# west-comms-hardware.net
KiCad netlist of a schematic drawn in EAGLE
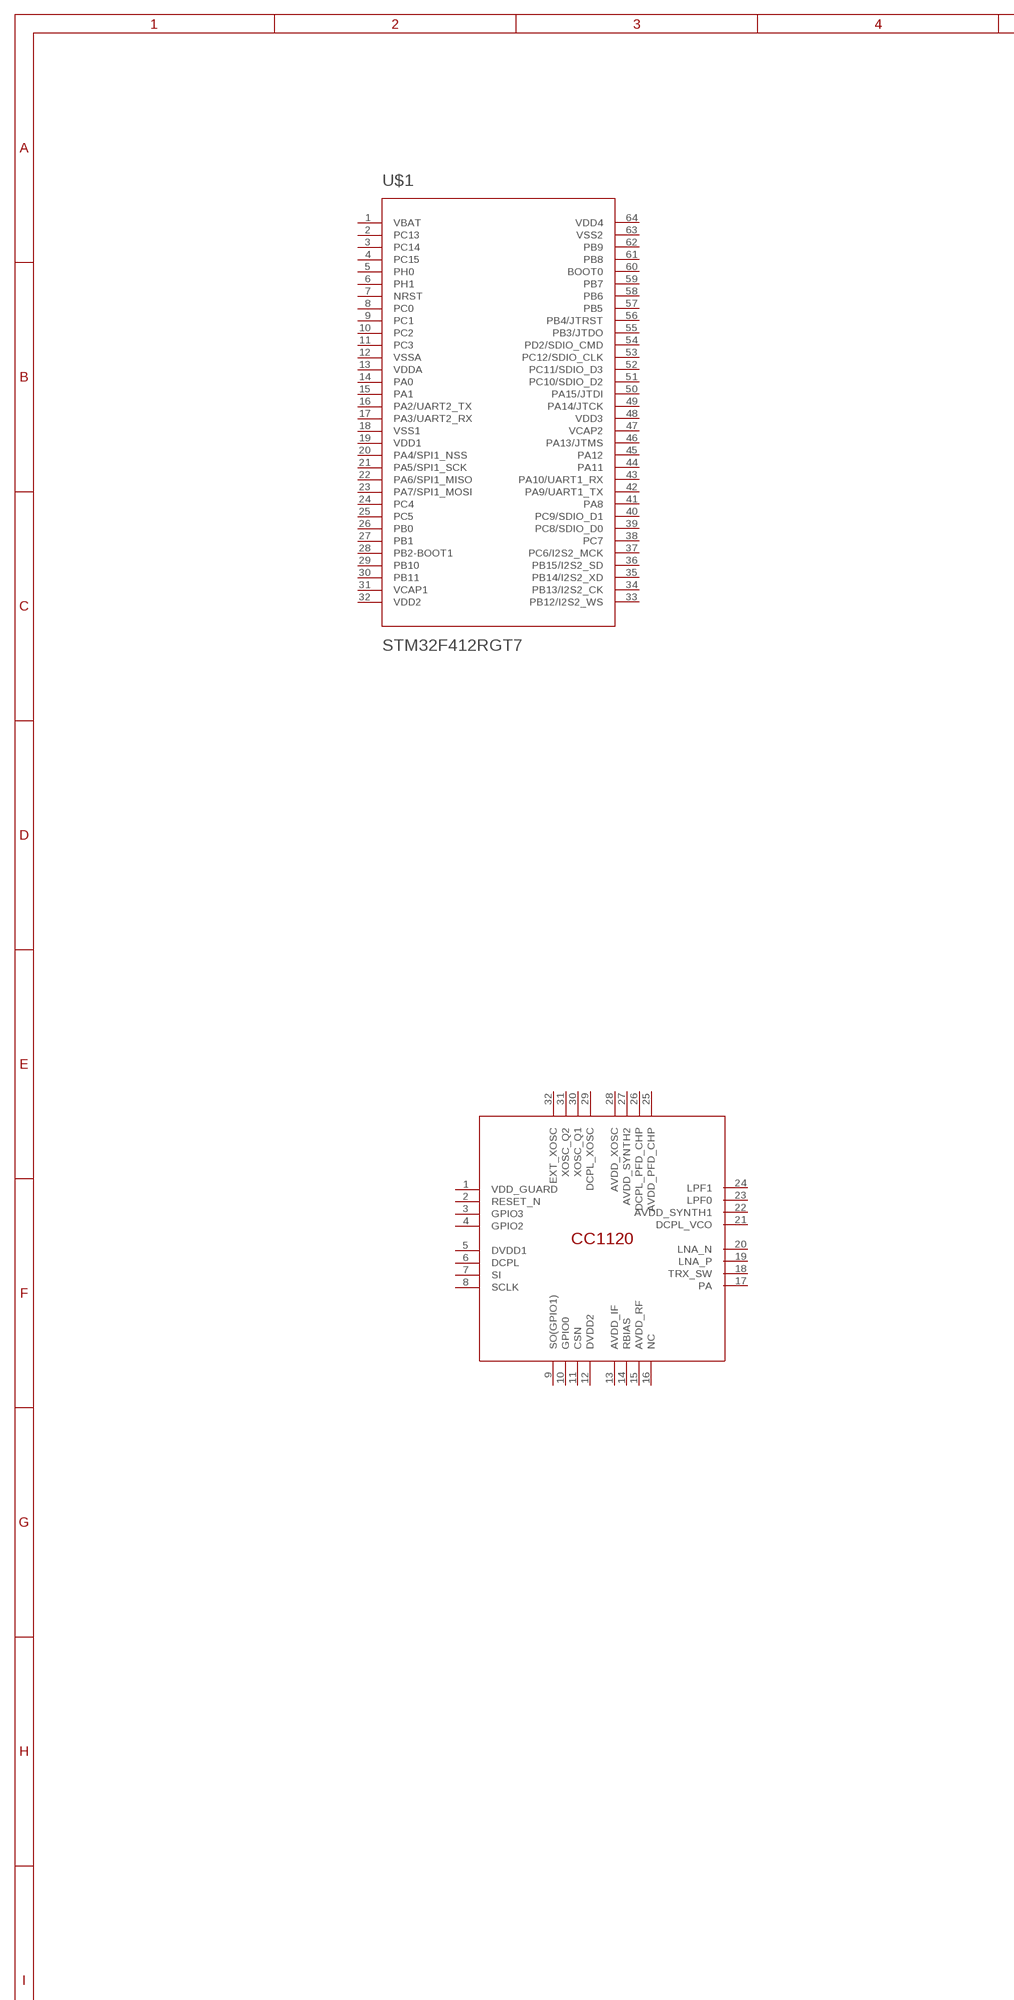
[diagram p0: schematic, sheet 1, part 1 of 2]
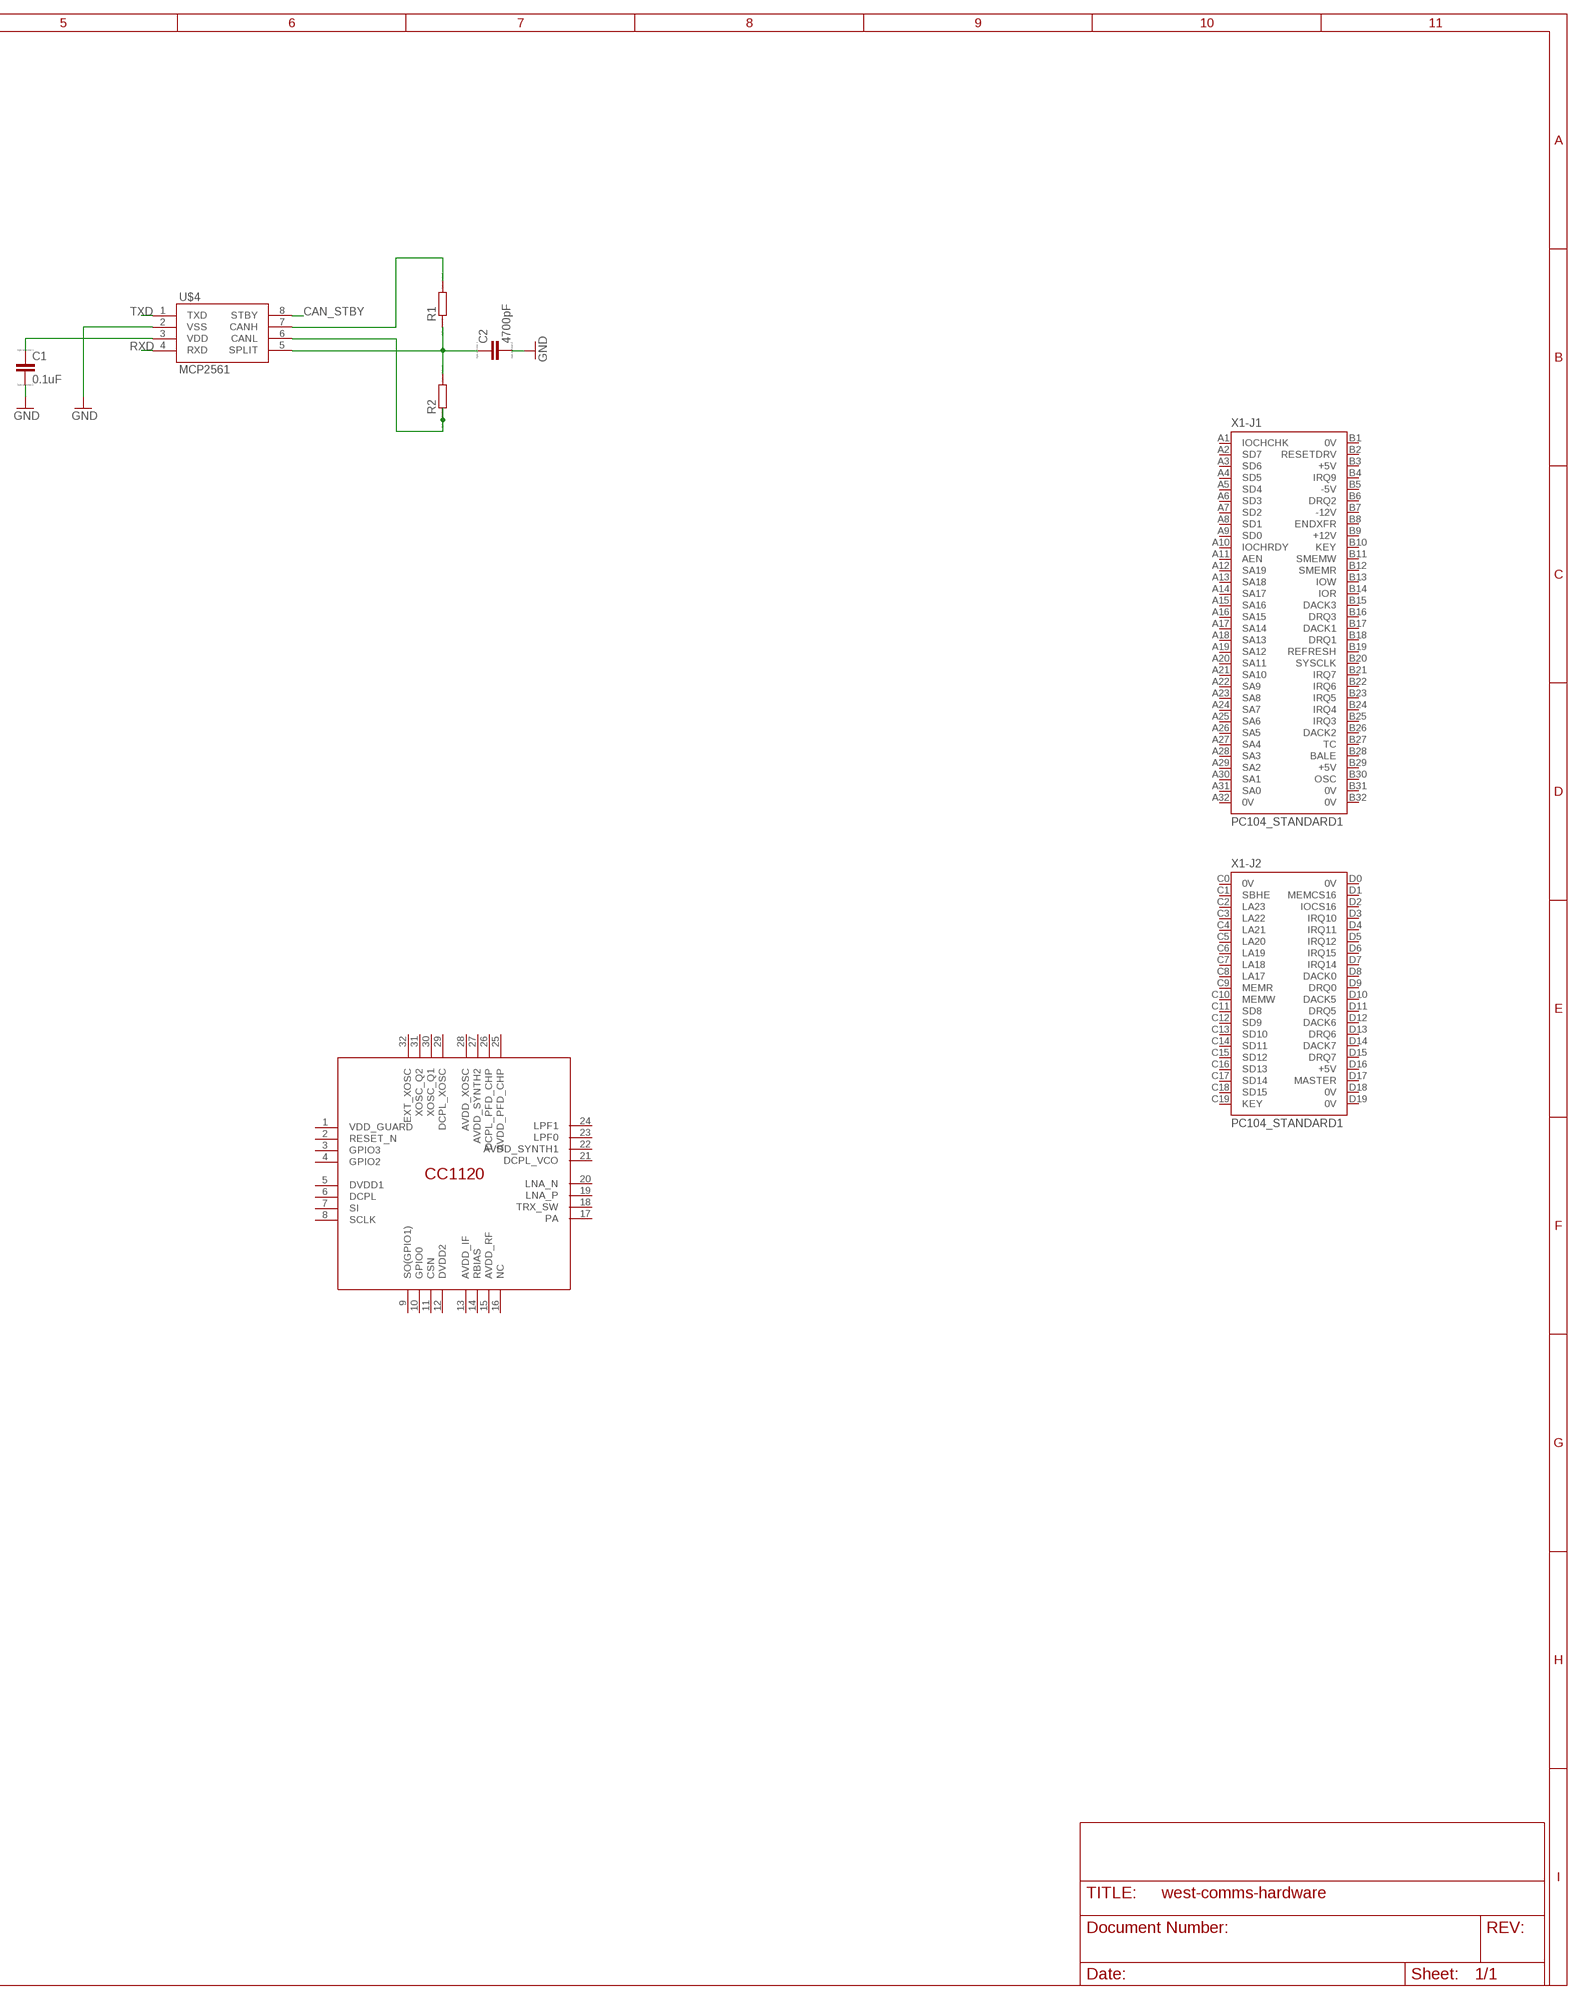
[diagram p1: schematic, sheet 1, part 2 of 2]

(export (version "E")
  (design (tool "Eeschema 10.0.6"))
  (components
    (comp (ref "C1")
      (value "0.1uF")
      (footprint "eagle-import:C0603")
      (libsource (lib "eagle-import") (part "CC0603"))
    )
    (comp (ref "C2")
      (value "4700pF")
      (footprint "eagle-import:C0603")
      (libsource (lib "eagle-import") (part "CC0603"))
    )
    (comp (ref "R1")
      (value "RR0603")
      (footprint "eagle-import:R0603")
      (libsource (lib "eagle-import") (part "RR0603"))
    )
    (comp (ref "R2")
      (value "RR0603")
      (footprint "eagle-import:R0603")
      (libsource (lib "eagle-import") (part "RR0603"))
    )
    (comp (ref "U$1")
      (value "STM32F412RGT7")
      (footprint "eagle-import:TQFP64")
      (libsource (lib "eagle-import") (part "STM32F405RG"))
    )
    (comp (ref "U$2")
      (value "CC1120")
      (footprint "eagle-import:VQFN")
      (libsource (lib "eagle-import") (part "CC1120"))
    )
    (comp (ref "U$3")
      (value "CC1120")
      (footprint "eagle-import:VQFN")
      (libsource (lib "eagle-import") (part "CC1120"))
    )
    (comp (ref "U$4")
      (value "MCP2561")
      (footprint "eagle-import:SO08")
      (libsource (lib "eagle-import") (part "MCP2561"))
    )
    (comp (ref "X1")
      (value "PC104_STANDARD1")
      (footprint "eagle-import:PC104-STANDARD")
      (libsource (lib "eagle-import") (part "PC104_STANDARD1"))
    )
  )
  (nets
    (net (code "1") (name "/CAN_STBY") (class "Default")
      (node (ref "U$4") (pin "8") (pinfunction "STBY_8") (pintype "bidirectional"))
    )
    (net (code "2") (name "/RXD") (class "Default")
      (node (ref "U$4") (pin "4") (pinfunction "RXD_4") (pintype "bidirectional"))
    )
    (net (code "3") (name "/TXD") (class "Default")
      (node (ref "U$4") (pin "1") (pinfunction "TXD_1") (pintype "bidirectional"))
    )
    (net (code "4") (name "GND") (class "Default")
      (node (ref "C1") (pin "2") (pinfunction "2_2") (pintype "passive"))
      (node (ref "C2") (pin "2") (pinfunction "2_2") (pintype "passive"))
      (node (ref "U$4") (pin "2") (pinfunction "VSS_2") (pintype "bidirectional"))
    )
    (net (code "5") (name "Net-(U$4-CANH)") (class "Default")
      (node (ref "R1") (pin "2") (pinfunction "2_2") (pintype "passive"))
      (node (ref "U$4") (pin "7") (pinfunction "CANH_7") (pintype "bidirectional"))
    )
    (net (code "6") (name "Net-(U$4-CANL)") (class "Default")
      (node (ref "R2") (pin "1") (pinfunction "1_1") (pintype "passive"))
      (node (ref "U$4") (pin "6") (pinfunction "CANL_6") (pintype "bidirectional"))
    )
    (net (code "7") (name "Net-(U$4-SPLIT)") (class "Default")
      (node (ref "C2") (pin "1") (pinfunction "1_1") (pintype "passive"))
      (node (ref "R1") (pin "1") (pinfunction "1_1") (pintype "passive"))
      (node (ref "R2") (pin "2") (pinfunction "2_2") (pintype "passive"))
      (node (ref "U$4") (pin "5") (pinfunction "SPLIT_5") (pintype "bidirectional"))
    )
    (net (code "8") (name "Net-(U$4-VDD)") (class "Default")
      (node (ref "C1") (pin "1") (pinfunction "1_1") (pintype "passive"))
      (node (ref "U$4") (pin "3") (pinfunction "VDD_3") (pintype "bidirectional"))
    )
    (net (code "9") (name "unconnected-(U$1-BOOT0-Pad60)") (class "Default")
      (node (ref "U$1") (pin "60") (pinfunction "BOOT0_60") (pintype "bidirectional"))
    )
    (net (code "10") (name "unconnected-(U$1-NRST-Pad7)") (class "Default")
      (node (ref "U$1") (pin "7") (pinfunction "NRST_7") (pintype "bidirectional"))
    )
    (net (code "11") (name "unconnected-(U$1-PA0-Pad14)") (class "Default")
      (node (ref "U$1") (pin "14") (pinfunction "PA0_14") (pintype "bidirectional"))
    )
    (net (code "12") (name "unconnected-(U$1-PA1-Pad15)") (class "Default")
      (node (ref "U$1") (pin "15") (pinfunction "PA1_15") (pintype "bidirectional"))
    )
    (net (code "13") (name "unconnected-(U$1-PA2{slash}UART2_TX-Pad16)") (class "Default")
      (node (ref "U$1") (pin "16") (pinfunction "PA2/UART2_TX_16") (pintype "bidirectional"))
    )
    (net (code "14") (name "unconnected-(U$1-PA3{slash}UART2_RX-Pad17)") (class "Default")
      (node (ref "U$1") (pin "17") (pinfunction "PA3/UART2_RX_17") (pintype "bidirectional"))
    )
    (net (code "15") (name "unconnected-(U$1-PA4{slash}SPI1_NSS-Pad20)") (class "Default")
      (node (ref "U$1") (pin "20") (pinfunction "PA4/SPI1_NSS_20") (pintype "bidirectional"))
    )
    (net (code "16") (name "unconnected-(U$1-PA5{slash}SPI1_SCK-Pad21)") (class "Default")
      (node (ref "U$1") (pin "21") (pinfunction "PA5/SPI1_SCK_21") (pintype "bidirectional"))
    )
    (net (code "17") (name "unconnected-(U$1-PA6{slash}SPI1_MISO-Pad22)") (class "Default")
      (node (ref "U$1") (pin "22") (pinfunction "PA6/SPI1_MISO_22") (pintype "bidirectional"))
    )
    (net (code "18") (name "unconnected-(U$1-PA7{slash}SPI1_MOSI-Pad23)") (class "Default")
      (node (ref "U$1") (pin "23") (pinfunction "PA7/SPI1_MOSI_23") (pintype "bidirectional"))
    )
    (net (code "19") (name "unconnected-(U$1-PA8-Pad41)") (class "Default")
      (node (ref "U$1") (pin "41") (pinfunction "PA8_41") (pintype "bidirectional"))
    )
    (net (code "20") (name "unconnected-(U$1-PA9{slash}UART1_TX-Pad42)") (class "Default")
      (node (ref "U$1") (pin "42") (pinfunction "PA9/UART1_TX_42") (pintype "bidirectional"))
    )
    (net (code "21") (name "unconnected-(U$1-PA10{slash}UART1_RX-Pad43)") (class "Default")
      (node (ref "U$1") (pin "43") (pinfunction "PA10/UART1_RX_43") (pintype "bidirectional"))
    )
    (net (code "22") (name "unconnected-(U$1-PA11-Pad44)") (class "Default")
      (node (ref "U$1") (pin "44") (pinfunction "PA11_44") (pintype "bidirectional"))
    )
    (net (code "23") (name "unconnected-(U$1-PA12-Pad45)") (class "Default")
      (node (ref "U$1") (pin "45") (pinfunction "PA12_45") (pintype "bidirectional"))
    )
    (net (code "24") (name "unconnected-(U$1-PA13{slash}JTMS-Pad46)") (class "Default")
      (node (ref "U$1") (pin "46") (pinfunction "PA13/JTMS_46") (pintype "bidirectional"))
    )
    (net (code "25") (name "unconnected-(U$1-PA14{slash}JTCK-Pad49)") (class "Default")
      (node (ref "U$1") (pin "49") (pinfunction "PA14/JTCK_49") (pintype "bidirectional"))
    )
    (net (code "26") (name "unconnected-(U$1-PA15{slash}JTDI-Pad50)") (class "Default")
      (node (ref "U$1") (pin "50") (pinfunction "PA15/JTDI_50") (pintype "bidirectional"))
    )
    (net (code "27") (name "unconnected-(U$1-PB0-Pad26)") (class "Default")
      (node (ref "U$1") (pin "26") (pinfunction "PB0_26") (pintype "bidirectional"))
    )
    (net (code "28") (name "unconnected-(U$1-PB1-Pad27)") (class "Default")
      (node (ref "U$1") (pin "27") (pinfunction "PB1_27") (pintype "bidirectional"))
    )
    (net (code "29") (name "unconnected-(U$1-PB2-BOOT1-Pad28)") (class "Default")
      (node (ref "U$1") (pin "28") (pinfunction "PB2-BOOT1_28") (pintype "bidirectional"))
    )
    (net (code "30") (name "unconnected-(U$1-PB3{slash}JTDO-Pad55)") (class "Default")
      (node (ref "U$1") (pin "55") (pinfunction "PB3/JTDO_55") (pintype "bidirectional"))
    )
    (net (code "31") (name "unconnected-(U$1-PB4{slash}JTRST-Pad56)") (class "Default")
      (node (ref "U$1") (pin "56") (pinfunction "PB4/JTRST_56") (pintype "bidirectional"))
    )
    (net (code "32") (name "unconnected-(U$1-PB5-Pad57)") (class "Default")
      (node (ref "U$1") (pin "57") (pinfunction "PB5_57") (pintype "bidirectional"))
    )
    (net (code "33") (name "unconnected-(U$1-PB6-Pad58)") (class "Default")
      (node (ref "U$1") (pin "58") (pinfunction "PB6_58") (pintype "bidirectional"))
    )
    (net (code "34") (name "unconnected-(U$1-PB7-Pad59)") (class "Default")
      (node (ref "U$1") (pin "59") (pinfunction "PB7_59") (pintype "bidirectional"))
    )
    (net (code "35") (name "unconnected-(U$1-PB8-Pad61)") (class "Default")
      (node (ref "U$1") (pin "61") (pinfunction "PB8_61") (pintype "bidirectional"))
    )
    (net (code "36") (name "unconnected-(U$1-PB9-Pad62)") (class "Default")
      (node (ref "U$1") (pin "62") (pinfunction "PB9_62") (pintype "bidirectional"))
    )
    (net (code "37") (name "unconnected-(U$1-PB10-Pad29)") (class "Default")
      (node (ref "U$1") (pin "29") (pinfunction "PB10_29") (pintype "bidirectional"))
    )
    (net (code "38") (name "unconnected-(U$1-PB11-Pad30)") (class "Default")
      (node (ref "U$1") (pin "30") (pinfunction "PB11_30") (pintype "bidirectional"))
    )
    (net (code "39") (name "unconnected-(U$1-PB12{slash}I2S2_WS-Pad33)") (class "Default")
      (node (ref "U$1") (pin "33") (pinfunction "PB12/I2S2_WS_33") (pintype "bidirectional"))
    )
    (net (code "40") (name "unconnected-(U$1-PB13{slash}I2S2_CK-Pad34)") (class "Default")
      (node (ref "U$1") (pin "34") (pinfunction "PB13/I2S2_CK_34") (pintype "bidirectional"))
    )
    (net (code "41") (name "unconnected-(U$1-PB14{slash}I2S2_XD-Pad35)") (class "Default")
      (node (ref "U$1") (pin "35") (pinfunction "PB14/I2S2_XD_35") (pintype "bidirectional"))
    )
    (net (code "42") (name "unconnected-(U$1-PB15{slash}I2S2_SD-Pad36)") (class "Default")
      (node (ref "U$1") (pin "36") (pinfunction "PB15/I2S2_SD_36") (pintype "bidirectional"))
    )
    (net (code "43") (name "unconnected-(U$1-PC0-Pad8)") (class "Default")
      (node (ref "U$1") (pin "8") (pinfunction "PC0_8") (pintype "bidirectional"))
    )
    (net (code "44") (name "unconnected-(U$1-PC1-Pad9)") (class "Default")
      (node (ref "U$1") (pin "9") (pinfunction "PC1_9") (pintype "bidirectional"))
    )
    (net (code "45") (name "unconnected-(U$1-PC2-Pad10)") (class "Default")
      (node (ref "U$1") (pin "10") (pinfunction "PC2_10") (pintype "bidirectional"))
    )
    (net (code "46") (name "unconnected-(U$1-PC3-Pad11)") (class "Default")
      (node (ref "U$1") (pin "11") (pinfunction "PC3_11") (pintype "bidirectional"))
    )
    (net (code "47") (name "unconnected-(U$1-PC4-Pad24)") (class "Default")
      (node (ref "U$1") (pin "24") (pinfunction "PC4_24") (pintype "bidirectional"))
    )
    (net (code "48") (name "unconnected-(U$1-PC5-Pad25)") (class "Default")
      (node (ref "U$1") (pin "25") (pinfunction "PC5_25") (pintype "bidirectional"))
    )
    (net (code "49") (name "unconnected-(U$1-PC6{slash}I2S2_MCK-Pad37)") (class "Default")
      (node (ref "U$1") (pin "37") (pinfunction "PC6/I2S2_MCK_37") (pintype "bidirectional"))
    )
    (net (code "50") (name "unconnected-(U$1-PC7-Pad38)") (class "Default")
      (node (ref "U$1") (pin "38") (pinfunction "PC7_38") (pintype "bidirectional"))
    )
    (net (code "51") (name "unconnected-(U$1-PC8{slash}SDIO_D0-Pad39)") (class "Default")
      (node (ref "U$1") (pin "39") (pinfunction "PC8/SDIO_D0_39") (pintype "bidirectional"))
    )
    (net (code "52") (name "unconnected-(U$1-PC9{slash}SDIO_D1-Pad40)") (class "Default")
      (node (ref "U$1") (pin "40") (pinfunction "PC9/SDIO_D1_40") (pintype "bidirectional"))
    )
    (net (code "53") (name "unconnected-(U$1-PC10{slash}SDIO_D2-Pad51)") (class "Default")
      (node (ref "U$1") (pin "51") (pinfunction "PC10/SDIO_D2_51") (pintype "bidirectional"))
    )
    (net (code "54") (name "unconnected-(U$1-PC11{slash}SDIO_D3-Pad52)") (class "Default")
      (node (ref "U$1") (pin "52") (pinfunction "PC11/SDIO_D3_52") (pintype "bidirectional"))
    )
    (net (code "55") (name "unconnected-(U$1-PC12{slash}SDIO_CLK-Pad53)") (class "Default")
      (node (ref "U$1") (pin "53") (pinfunction "PC12/SDIO_CLK_53") (pintype "bidirectional"))
    )
    (net (code "56") (name "unconnected-(U$1-PC13-Pad2)") (class "Default")
      (node (ref "U$1") (pin "2") (pinfunction "PC13_2") (pintype "bidirectional"))
    )
    (net (code "57") (name "unconnected-(U$1-PC14-Pad3)") (class "Default")
      (node (ref "U$1") (pin "3") (pinfunction "PC14_3") (pintype "bidirectional"))
    )
    (net (code "58") (name "unconnected-(U$1-PC15-Pad4)") (class "Default")
      (node (ref "U$1") (pin "4") (pinfunction "PC15_4") (pintype "bidirectional"))
    )
    (net (code "59") (name "unconnected-(U$1-PD2{slash}SDIO_CMD-Pad54)") (class "Default")
      (node (ref "U$1") (pin "54") (pinfunction "PD2/SDIO_CMD_54") (pintype "bidirectional"))
    )
    (net (code "60") (name "unconnected-(U$1-PH0-Pad5)") (class "Default")
      (node (ref "U$1") (pin "5") (pinfunction "PH0_5") (pintype "bidirectional"))
    )
    (net (code "61") (name "unconnected-(U$1-PH1-Pad6)") (class "Default")
      (node (ref "U$1") (pin "6") (pinfunction "PH1_6") (pintype "bidirectional"))
    )
    (net (code "62") (name "unconnected-(U$1-VBAT-Pad1)") (class "Default")
      (node (ref "U$1") (pin "1") (pinfunction "VBAT_1") (pintype "bidirectional"))
    )
    (net (code "63") (name "unconnected-(U$1-VCAP1-Pad31)") (class "Default")
      (node (ref "U$1") (pin "31") (pinfunction "VCAP1_31") (pintype "bidirectional"))
    )
    (net (code "64") (name "unconnected-(U$1-VCAP2-Pad47)") (class "Default")
      (node (ref "U$1") (pin "47") (pinfunction "VCAP2_47") (pintype "bidirectional"))
    )
    (net (code "65") (name "unconnected-(U$1-VDD1-Pad19)") (class "Default")
      (node (ref "U$1") (pin "19") (pinfunction "VDD1_19") (pintype "bidirectional"))
    )
    (net (code "66") (name "unconnected-(U$1-VDD2-Pad32)") (class "Default")
      (node (ref "U$1") (pin "32") (pinfunction "VDD2_32") (pintype "bidirectional"))
    )
    (net (code "67") (name "unconnected-(U$1-VDD3-Pad48)") (class "Default")
      (node (ref "U$1") (pin "48") (pinfunction "VDD3_48") (pintype "bidirectional"))
    )
    (net (code "68") (name "unconnected-(U$1-VDD4-Pad64)") (class "Default")
      (node (ref "U$1") (pin "64") (pinfunction "VDD4_64") (pintype "bidirectional"))
    )
    (net (code "69") (name "unconnected-(U$1-VDDA-Pad13)") (class "Default")
      (node (ref "U$1") (pin "13") (pinfunction "VDDA_13") (pintype "bidirectional"))
    )
    (net (code "70") (name "unconnected-(U$1-VSS1-Pad18)") (class "Default")
      (node (ref "U$1") (pin "18") (pinfunction "VSS1_18") (pintype "bidirectional"))
    )
    (net (code "71") (name "unconnected-(U$1-VSS2-Pad63)") (class "Default")
      (node (ref "U$1") (pin "63") (pinfunction "VSS2_63") (pintype "bidirectional"))
    )
    (net (code "72") (name "unconnected-(U$1-VSSA-Pad12)") (class "Default")
      (node (ref "U$1") (pin "12") (pinfunction "VSSA_12") (pintype "bidirectional"))
    )
    (net (code "73") (name "unconnected-(U$2-AVDD_IF-Pad13)") (class "Default")
      (node (ref "U$2") (pin "13") (pinfunction "AVDD_IF_13") (pintype "bidirectional"))
    )
    (net (code "74") (name "unconnected-(U$2-AVDD_PFD_CHP-Pad25)") (class "Default")
      (node (ref "U$2") (pin "25") (pinfunction "AVDD_PFD_CHP_25") (pintype "bidirectional"))
    )
    (net (code "75") (name "unconnected-(U$2-AVDD_RF-Pad15)") (class "Default")
      (node (ref "U$2") (pin "15") (pinfunction "AVDD_RF_15") (pintype "bidirectional"))
    )
    (net (code "76") (name "unconnected-(U$2-AVDD_SYNTH1-Pad22)") (class "Default")
      (node (ref "U$2") (pin "22") (pinfunction "AVDD_SYNTH1_22") (pintype "bidirectional"))
    )
    (net (code "77") (name "unconnected-(U$2-AVDD_SYNTH2-Pad27)") (class "Default")
      (node (ref "U$2") (pin "27") (pinfunction "AVDD_SYNTH2_27") (pintype "bidirectional"))
    )
    (net (code "78") (name "unconnected-(U$2-AVDD_XOSC-Pad28)") (class "Default")
      (node (ref "U$2") (pin "28") (pinfunction "AVDD_XOSC_28") (pintype "bidirectional"))
    )
    (net (code "79") (name "unconnected-(U$2-CSN-Pad11)") (class "Default")
      (node (ref "U$2") (pin "11") (pinfunction "CSN_11") (pintype "bidirectional"))
    )
    (net (code "80") (name "unconnected-(U$2-DCPL-Pad6)") (class "Default")
      (node (ref "U$2") (pin "6") (pinfunction "DCPL_6") (pintype "bidirectional"))
    )
    (net (code "81") (name "unconnected-(U$2-DCPL_PFD_CHP-Pad26)") (class "Default")
      (node (ref "U$2") (pin "26") (pinfunction "DCPL_PFD_CHP_26") (pintype "bidirectional"))
    )
    (net (code "82") (name "unconnected-(U$2-DCPL_VCO-Pad21)") (class "Default")
      (node (ref "U$2") (pin "21") (pinfunction "DCPL_VCO_21") (pintype "bidirectional"))
    )
    (net (code "83") (name "unconnected-(U$2-DCPL_XOSC-Pad29)") (class "Default")
      (node (ref "U$2") (pin "29") (pinfunction "DCPL_XOSC_29") (pintype "bidirectional"))
    )
    (net (code "84") (name "unconnected-(U$2-DVDD1-Pad5)") (class "Default")
      (node (ref "U$2") (pin "5") (pinfunction "DVDD1_5") (pintype "bidirectional"))
    )
    (net (code "85") (name "unconnected-(U$2-DVDD2-Pad12)") (class "Default")
      (node (ref "U$2") (pin "12") (pinfunction "DVDD2_12") (pintype "bidirectional"))
    )
    (net (code "86") (name "unconnected-(U$2-EXT_XOSC-Pad32)") (class "Default")
      (node (ref "U$2") (pin "32") (pinfunction "EXT_XOSC_32") (pintype "bidirectional"))
    )
    (net (code "87") (name "unconnected-(U$2-GPIO0-Pad10)") (class "Default")
      (node (ref "U$2") (pin "10") (pinfunction "GPIO0_10") (pintype "bidirectional"))
    )
    (net (code "88") (name "unconnected-(U$2-GPIO2-Pad4)") (class "Default")
      (node (ref "U$2") (pin "4") (pinfunction "GPIO2_4") (pintype "bidirectional"))
    )
    (net (code "89") (name "unconnected-(U$2-GPIO3-Pad3)") (class "Default")
      (node (ref "U$2") (pin "3") (pinfunction "GPIO3_3") (pintype "bidirectional"))
    )
    (net (code "90") (name "unconnected-(U$2-LNA_N-Pad20)") (class "Default")
      (node (ref "U$2") (pin "20") (pinfunction "LNA_N_20") (pintype "bidirectional"))
    )
    (net (code "91") (name "unconnected-(U$2-LNA_P-Pad19)") (class "Default")
      (node (ref "U$2") (pin "19") (pinfunction "LNA_P_19") (pintype "bidirectional"))
    )
    (net (code "92") (name "unconnected-(U$2-LPF0-Pad23)") (class "Default")
      (node (ref "U$2") (pin "23") (pinfunction "LPF0_23") (pintype "bidirectional"))
    )
    (net (code "93") (name "unconnected-(U$2-LPF1-Pad24)") (class "Default")
      (node (ref "U$2") (pin "24") (pinfunction "LPF1_24") (pintype "bidirectional"))
    )
    (net (code "94") (name "unconnected-(U$2-NC-Pad16)") (class "Default")
      (node (ref "U$2") (pin "16") (pinfunction "NC_16") (pintype "bidirectional"))
    )
    (net (code "95") (name "unconnected-(U$2-PA-Pad17)") (class "Default")
      (node (ref "U$2") (pin "17") (pinfunction "PA_17") (pintype "bidirectional"))
    )
    (net (code "96") (name "unconnected-(U$2-RBIAS-Pad14)") (class "Default")
      (node (ref "U$2") (pin "14") (pinfunction "RBIAS_14") (pintype "bidirectional"))
    )
    (net (code "97") (name "unconnected-(U$2-RESET_N-Pad2)") (class "Default")
      (node (ref "U$2") (pin "2") (pinfunction "RESET_N_2") (pintype "bidirectional"))
    )
    (net (code "98") (name "unconnected-(U$2-SCLK-Pad8)") (class "Default")
      (node (ref "U$2") (pin "8") (pinfunction "SCLK_8") (pintype "bidirectional"))
    )
    (net (code "99") (name "unconnected-(U$2-SI-Pad7)") (class "Default")
      (node (ref "U$2") (pin "7") (pinfunction "SI_7") (pintype "bidirectional"))
    )
    (net (code "100") (name "unconnected-(U$2-SO(GPIO1)-Pad9)") (class "Default")
      (node (ref "U$2") (pin "9") (pinfunction "SO(GPIO1)_9") (pintype "bidirectional"))
    )
    (net (code "101") (name "unconnected-(U$2-TRX_SW-Pad18)") (class "Default")
      (node (ref "U$2") (pin "18") (pinfunction "TRX_SW_18") (pintype "bidirectional"))
    )
    (net (code "102") (name "unconnected-(U$2-VDD_GUARD-Pad1)") (class "Default")
      (node (ref "U$2") (pin "1") (pinfunction "VDD_GUARD_1") (pintype "bidirectional"))
    )
    (net (code "103") (name "unconnected-(U$2-XOSC_Q1-Pad30)") (class "Default")
      (node (ref "U$2") (pin "30") (pinfunction "XOSC_Q1_30") (pintype "bidirectional"))
    )
    (net (code "104") (name "unconnected-(U$2-XOSC_Q2-Pad31)") (class "Default")
      (node (ref "U$2") (pin "31") (pinfunction "XOSC_Q2_31") (pintype "bidirectional"))
    )
    (net (code "105") (name "unconnected-(U$3-AVDD_IF-Pad13)") (class "Default")
      (node (ref "U$3") (pin "13") (pinfunction "AVDD_IF_13") (pintype "bidirectional"))
    )
    (net (code "106") (name "unconnected-(U$3-AVDD_PFD_CHP-Pad25)") (class "Default")
      (node (ref "U$3") (pin "25") (pinfunction "AVDD_PFD_CHP_25") (pintype "bidirectional"))
    )
    (net (code "107") (name "unconnected-(U$3-AVDD_RF-Pad15)") (class "Default")
      (node (ref "U$3") (pin "15") (pinfunction "AVDD_RF_15") (pintype "bidirectional"))
    )
    (net (code "108") (name "unconnected-(U$3-AVDD_SYNTH1-Pad22)") (class "Default")
      (node (ref "U$3") (pin "22") (pinfunction "AVDD_SYNTH1_22") (pintype "bidirectional"))
    )
    (net (code "109") (name "unconnected-(U$3-AVDD_SYNTH2-Pad27)") (class "Default")
      (node (ref "U$3") (pin "27") (pinfunction "AVDD_SYNTH2_27") (pintype "bidirectional"))
    )
    (net (code "110") (name "unconnected-(U$3-AVDD_XOSC-Pad28)") (class "Default")
      (node (ref "U$3") (pin "28") (pinfunction "AVDD_XOSC_28") (pintype "bidirectional"))
    )
    (net (code "111") (name "unconnected-(U$3-CSN-Pad11)") (class "Default")
      (node (ref "U$3") (pin "11") (pinfunction "CSN_11") (pintype "bidirectional"))
    )
    (net (code "112") (name "unconnected-(U$3-DCPL-Pad6)") (class "Default")
      (node (ref "U$3") (pin "6") (pinfunction "DCPL_6") (pintype "bidirectional"))
    )
    (net (code "113") (name "unconnected-(U$3-DCPL_PFD_CHP-Pad26)") (class "Default")
      (node (ref "U$3") (pin "26") (pinfunction "DCPL_PFD_CHP_26") (pintype "bidirectional"))
    )
    (net (code "114") (name "unconnected-(U$3-DCPL_VCO-Pad21)") (class "Default")
      (node (ref "U$3") (pin "21") (pinfunction "DCPL_VCO_21") (pintype "bidirectional"))
    )
    (net (code "115") (name "unconnected-(U$3-DCPL_XOSC-Pad29)") (class "Default")
      (node (ref "U$3") (pin "29") (pinfunction "DCPL_XOSC_29") (pintype "bidirectional"))
    )
    (net (code "116") (name "unconnected-(U$3-DVDD1-Pad5)") (class "Default")
      (node (ref "U$3") (pin "5") (pinfunction "DVDD1_5") (pintype "bidirectional"))
    )
    (net (code "117") (name "unconnected-(U$3-DVDD2-Pad12)") (class "Default")
      (node (ref "U$3") (pin "12") (pinfunction "DVDD2_12") (pintype "bidirectional"))
    )
    (net (code "118") (name "unconnected-(U$3-EXT_XOSC-Pad32)") (class "Default")
      (node (ref "U$3") (pin "32") (pinfunction "EXT_XOSC_32") (pintype "bidirectional"))
    )
    (net (code "119") (name "unconnected-(U$3-GPIO0-Pad10)") (class "Default")
      (node (ref "U$3") (pin "10") (pinfunction "GPIO0_10") (pintype "bidirectional"))
    )
    (net (code "120") (name "unconnected-(U$3-GPIO2-Pad4)") (class "Default")
      (node (ref "U$3") (pin "4") (pinfunction "GPIO2_4") (pintype "bidirectional"))
    )
    (net (code "121") (name "unconnected-(U$3-GPIO3-Pad3)") (class "Default")
      (node (ref "U$3") (pin "3") (pinfunction "GPIO3_3") (pintype "bidirectional"))
    )
    (net (code "122") (name "unconnected-(U$3-LNA_N-Pad20)") (class "Default")
      (node (ref "U$3") (pin "20") (pinfunction "LNA_N_20") (pintype "bidirectional"))
    )
    (net (code "123") (name "unconnected-(U$3-LNA_P-Pad19)") (class "Default")
      (node (ref "U$3") (pin "19") (pinfunction "LNA_P_19") (pintype "bidirectional"))
    )
    (net (code "124") (name "unconnected-(U$3-LPF0-Pad23)") (class "Default")
      (node (ref "U$3") (pin "23") (pinfunction "LPF0_23") (pintype "bidirectional"))
    )
    (net (code "125") (name "unconnected-(U$3-LPF1-Pad24)") (class "Default")
      (node (ref "U$3") (pin "24") (pinfunction "LPF1_24") (pintype "bidirectional"))
    )
    (net (code "126") (name "unconnected-(U$3-NC-Pad16)") (class "Default")
      (node (ref "U$3") (pin "16") (pinfunction "NC_16") (pintype "bidirectional"))
    )
    (net (code "127") (name "unconnected-(U$3-PA-Pad17)") (class "Default")
      (node (ref "U$3") (pin "17") (pinfunction "PA_17") (pintype "bidirectional"))
    )
    (net (code "128") (name "unconnected-(U$3-RBIAS-Pad14)") (class "Default")
      (node (ref "U$3") (pin "14") (pinfunction "RBIAS_14") (pintype "bidirectional"))
    )
    (net (code "129") (name "unconnected-(U$3-RESET_N-Pad2)") (class "Default")
      (node (ref "U$3") (pin "2") (pinfunction "RESET_N_2") (pintype "bidirectional"))
    )
    (net (code "130") (name "unconnected-(U$3-SCLK-Pad8)") (class "Default")
      (node (ref "U$3") (pin "8") (pinfunction "SCLK_8") (pintype "bidirectional"))
    )
    (net (code "131") (name "unconnected-(U$3-SI-Pad7)") (class "Default")
      (node (ref "U$3") (pin "7") (pinfunction "SI_7") (pintype "bidirectional"))
    )
    (net (code "132") (name "unconnected-(U$3-SO(GPIO1)-Pad9)") (class "Default")
      (node (ref "U$3") (pin "9") (pinfunction "SO(GPIO1)_9") (pintype "bidirectional"))
    )
    (net (code "133") (name "unconnected-(U$3-TRX_SW-Pad18)") (class "Default")
      (node (ref "U$3") (pin "18") (pinfunction "TRX_SW_18") (pintype "bidirectional"))
    )
    (net (code "134") (name "unconnected-(U$3-VDD_GUARD-Pad1)") (class "Default")
      (node (ref "U$3") (pin "1") (pinfunction "VDD_GUARD_1") (pintype "bidirectional"))
    )
    (net (code "135") (name "unconnected-(U$3-XOSC_Q1-Pad30)") (class "Default")
      (node (ref "U$3") (pin "30") (pinfunction "XOSC_Q1_30") (pintype "bidirectional"))
    )
    (net (code "136") (name "unconnected-(U$3-XOSC_Q2-Pad31)") (class "Default")
      (node (ref "U$3") (pin "31") (pinfunction "XOSC_Q2_31") (pintype "bidirectional"))
    )
    (net (code "137") (name "unconnected-(X1A-+5V-PadB3)") (class "Default")
      (node (ref "X1") (pin "B3") (pinfunction "+5V_B3") (pintype "passive"))
    )
    (net (code "138") (name "unconnected-(X1A-+5V-PadB29)") (class "Default")
      (node (ref "X1") (pin "B29") (pinfunction "+5V_B29") (pintype "passive"))
    )
    (net (code "139") (name "unconnected-(X1A-+12V-PadB9)") (class "Default")
      (node (ref "X1") (pin "B9") (pinfunction "+12V_B9") (pintype "passive"))
    )
    (net (code "140") (name "unconnected-(X1A--5V-PadB5)") (class "Default")
      (node (ref "X1") (pin "B5") (pinfunction "-5V_B5") (pintype "passive"))
    )
    (net (code "141") (name "unconnected-(X1A--12V-PadB7)") (class "Default")
      (node (ref "X1") (pin "B7") (pinfunction "-12V_B7") (pintype "passive"))
    )
    (net (code "142") (name "unconnected-(X1A-0V-PadA32)") (class "Default")
      (node (ref "X1") (pin "A32") (pinfunction "0V_A32") (pintype "passive"))
    )
    (net (code "143") (name "unconnected-(X1A-0V-PadB1)") (class "Default")
      (node (ref "X1") (pin "B1") (pinfunction "0V_B1") (pintype "passive"))
    )
    (net (code "144") (name "unconnected-(X1A-0V-PadB31)") (class "Default")
      (node (ref "X1") (pin "B31") (pinfunction "0V_B31") (pintype "passive"))
    )
    (net (code "145") (name "unconnected-(X1A-0V-PadB32)") (class "Default")
      (node (ref "X1") (pin "B32") (pinfunction "0V_B32") (pintype "passive"))
    )
    (net (code "146") (name "unconnected-(X1A-AEN-PadA11)") (class "Default")
      (node (ref "X1") (pin "A11") (pinfunction "AEN_A11") (pintype "passive"))
    )
    (net (code "147") (name "unconnected-(X1A-BALE-PadB28)") (class "Default")
      (node (ref "X1") (pin "B28") (pinfunction "BALE_B28") (pintype "passive"))
    )
    (net (code "148") (name "unconnected-(X1A-DACK1-PadB17)") (class "Default")
      (node (ref "X1") (pin "B17") (pinfunction "DACK1_B17") (pintype "passive"))
    )
    (net (code "149") (name "unconnected-(X1A-DACK2-PadB26)") (class "Default")
      (node (ref "X1") (pin "B26") (pinfunction "DACK2_B26") (pintype "passive"))
    )
    (net (code "150") (name "unconnected-(X1A-DACK3-PadB15)") (class "Default")
      (node (ref "X1") (pin "B15") (pinfunction "DACK3_B15") (pintype "passive"))
    )
    (net (code "151") (name "unconnected-(X1A-DRQ1-PadB18)") (class "Default")
      (node (ref "X1") (pin "B18") (pinfunction "DRQ1_B18") (pintype "passive"))
    )
    (net (code "152") (name "unconnected-(X1A-DRQ2-PadB6)") (class "Default")
      (node (ref "X1") (pin "B6") (pinfunction "DRQ2_B6") (pintype "passive"))
    )
    (net (code "153") (name "unconnected-(X1A-DRQ3-PadB16)") (class "Default")
      (node (ref "X1") (pin "B16") (pinfunction "DRQ3_B16") (pintype "passive"))
    )
    (net (code "154") (name "unconnected-(X1A-ENDXFR-PadB8)") (class "Default")
      (node (ref "X1") (pin "B8") (pinfunction "ENDXFR_B8") (pintype "passive"))
    )
    (net (code "155") (name "unconnected-(X1A-IOCHCHK-PadA1)") (class "Default")
      (node (ref "X1") (pin "A1") (pinfunction "IOCHCHK_A1") (pintype "passive"))
    )
    (net (code "156") (name "unconnected-(X1A-IOCHRDY-PadA10)") (class "Default")
      (node (ref "X1") (pin "A10") (pinfunction "IOCHRDY_A10") (pintype "passive"))
    )
    (net (code "157") (name "unconnected-(X1A-IOR-PadB14)") (class "Default")
      (node (ref "X1") (pin "B14") (pinfunction "IOR_B14") (pintype "passive"))
    )
    (net (code "158") (name "unconnected-(X1A-IOW-PadB13)") (class "Default")
      (node (ref "X1") (pin "B13") (pinfunction "IOW_B13") (pintype "passive"))
    )
    (net (code "159") (name "unconnected-(X1A-IRQ3-PadB25)") (class "Default")
      (node (ref "X1") (pin "B25") (pinfunction "IRQ3_B25") (pintype "passive"))
    )
    (net (code "160") (name "unconnected-(X1A-IRQ4-PadB24)") (class "Default")
      (node (ref "X1") (pin "B24") (pinfunction "IRQ4_B24") (pintype "passive"))
    )
    (net (code "161") (name "unconnected-(X1A-IRQ5-PadB23)") (class "Default")
      (node (ref "X1") (pin "B23") (pinfunction "IRQ5_B23") (pintype "passive"))
    )
    (net (code "162") (name "unconnected-(X1A-IRQ6-PadB22)") (class "Default")
      (node (ref "X1") (pin "B22") (pinfunction "IRQ6_B22") (pintype "passive"))
    )
    (net (code "163") (name "unconnected-(X1A-IRQ7-PadB21)") (class "Default")
      (node (ref "X1") (pin "B21") (pinfunction "IRQ7_B21") (pintype "passive"))
    )
    (net (code "164") (name "unconnected-(X1A-IRQ9-PadB4)") (class "Default")
      (node (ref "X1") (pin "B4") (pinfunction "IRQ9_B4") (pintype "passive"))
    )
    (net (code "165") (name "unconnected-(X1A-KEY-PadB10)") (class "Default")
      (node (ref "X1") (pin "B10") (pinfunction "KEY_B10") (pintype "passive"))
    )
    (net (code "166") (name "unconnected-(X1A-OSC-PadB30)") (class "Default")
      (node (ref "X1") (pin "B30") (pinfunction "OSC_B30") (pintype "passive"))
    )
    (net (code "167") (name "unconnected-(X1A-REFRESH-PadB19)") (class "Default")
      (node (ref "X1") (pin "B19") (pinfunction "REFRESH_B19") (pintype "passive"))
    )
    (net (code "168") (name "unconnected-(X1A-RESETDRV-PadB2)") (class "Default")
      (node (ref "X1") (pin "B2") (pinfunction "RESETDRV_B2") (pintype "passive"))
    )
    (net (code "169") (name "unconnected-(X1A-SA0-PadA31)") (class "Default")
      (node (ref "X1") (pin "A31") (pinfunction "SA0_A31") (pintype "passive"))
    )
    (net (code "170") (name "unconnected-(X1A-SA1-PadA30)") (class "Default")
      (node (ref "X1") (pin "A30") (pinfunction "SA1_A30") (pintype "passive"))
    )
    (net (code "171") (name "unconnected-(X1A-SA2-PadA29)") (class "Default")
      (node (ref "X1") (pin "A29") (pinfunction "SA2_A29") (pintype "passive"))
    )
    (net (code "172") (name "unconnected-(X1A-SA3-PadA28)") (class "Default")
      (node (ref "X1") (pin "A28") (pinfunction "SA3_A28") (pintype "passive"))
    )
    (net (code "173") (name "unconnected-(X1A-SA4-PadA27)") (class "Default")
      (node (ref "X1") (pin "A27") (pinfunction "SA4_A27") (pintype "passive"))
    )
    (net (code "174") (name "unconnected-(X1A-SA5-PadA26)") (class "Default")
      (node (ref "X1") (pin "A26") (pinfunction "SA5_A26") (pintype "passive"))
    )
    (net (code "175") (name "unconnected-(X1A-SA6-PadA25)") (class "Default")
      (node (ref "X1") (pin "A25") (pinfunction "SA6_A25") (pintype "passive"))
    )
    (net (code "176") (name "unconnected-(X1A-SA7-PadA24)") (class "Default")
      (node (ref "X1") (pin "A24") (pinfunction "SA7_A24") (pintype "passive"))
    )
    (net (code "177") (name "unconnected-(X1A-SA8-PadA23)") (class "Default")
      (node (ref "X1") (pin "A23") (pinfunction "SA8_A23") (pintype "passive"))
    )
    (net (code "178") (name "unconnected-(X1A-SA9-PadA22)") (class "Default")
      (node (ref "X1") (pin "A22") (pinfunction "SA9_A22") (pintype "passive"))
    )
    (net (code "179") (name "unconnected-(X1A-SA10-PadA21)") (class "Default")
      (node (ref "X1") (pin "A21") (pinfunction "SA10_A21") (pintype "passive"))
    )
    (net (code "180") (name "unconnected-(X1A-SA11-PadA20)") (class "Default")
      (node (ref "X1") (pin "A20") (pinfunction "SA11_A20") (pintype "passive"))
    )
    (net (code "181") (name "unconnected-(X1A-SA12-PadA19)") (class "Default")
      (node (ref "X1") (pin "A19") (pinfunction "SA12_A19") (pintype "passive"))
    )
    (net (code "182") (name "unconnected-(X1A-SA13-PadA18)") (class "Default")
      (node (ref "X1") (pin "A18") (pinfunction "SA13_A18") (pintype "passive"))
    )
    (net (code "183") (name "unconnected-(X1A-SA14-PadA17)") (class "Default")
      (node (ref "X1") (pin "A17") (pinfunction "SA14_A17") (pintype "passive"))
    )
    (net (code "184") (name "unconnected-(X1A-SA15-PadA16)") (class "Default")
      (node (ref "X1") (pin "A16") (pinfunction "SA15_A16") (pintype "passive"))
    )
    (net (code "185") (name "unconnected-(X1A-SA16-PadA15)") (class "Default")
      (node (ref "X1") (pin "A15") (pinfunction "SA16_A15") (pintype "passive"))
    )
    (net (code "186") (name "unconnected-(X1A-SA17-PadA14)") (class "Default")
      (node (ref "X1") (pin "A14") (pinfunction "SA17_A14") (pintype "passive"))
    )
    (net (code "187") (name "unconnected-(X1A-SA18-PadA13)") (class "Default")
      (node (ref "X1") (pin "A13") (pinfunction "SA18_A13") (pintype "passive"))
    )
    (net (code "188") (name "unconnected-(X1A-SA19-PadA12)") (class "Default")
      (node (ref "X1") (pin "A12") (pinfunction "SA19_A12") (pintype "passive"))
    )
    (net (code "189") (name "unconnected-(X1A-SD0-PadA9)") (class "Default")
      (node (ref "X1") (pin "A9") (pinfunction "SD0_A9") (pintype "passive"))
    )
    (net (code "190") (name "unconnected-(X1A-SD1-PadA8)") (class "Default")
      (node (ref "X1") (pin "A8") (pinfunction "SD1_A8") (pintype "passive"))
    )
    (net (code "191") (name "unconnected-(X1A-SD2-PadA7)") (class "Default")
      (node (ref "X1") (pin "A7") (pinfunction "SD2_A7") (pintype "passive"))
    )
    (net (code "192") (name "unconnected-(X1A-SD3-PadA6)") (class "Default")
      (node (ref "X1") (pin "A6") (pinfunction "SD3_A6") (pintype "passive"))
    )
    (net (code "193") (name "unconnected-(X1A-SD4-PadA5)") (class "Default")
      (node (ref "X1") (pin "A5") (pinfunction "SD4_A5") (pintype "passive"))
    )
    (net (code "194") (name "unconnected-(X1A-SD5-PadA4)") (class "Default")
      (node (ref "X1") (pin "A4") (pinfunction "SD5_A4") (pintype "passive"))
    )
    (net (code "195") (name "unconnected-(X1A-SD6-PadA3)") (class "Default")
      (node (ref "X1") (pin "A3") (pinfunction "SD6_A3") (pintype "passive"))
    )
    (net (code "196") (name "unconnected-(X1A-SD7-PadA2)") (class "Default")
      (node (ref "X1") (pin "A2") (pinfunction "SD7_A2") (pintype "passive"))
    )
    (net (code "197") (name "unconnected-(X1A-SMEMR-PadB12)") (class "Default")
      (node (ref "X1") (pin "B12") (pinfunction "SMEMR_B12") (pintype "passive"))
    )
    (net (code "198") (name "unconnected-(X1A-SMEMW-PadB11)") (class "Default")
      (node (ref "X1") (pin "B11") (pinfunction "SMEMW_B11") (pintype "passive"))
    )
    (net (code "199") (name "unconnected-(X1A-SYSCLK-PadB20)") (class "Default")
      (node (ref "X1") (pin "B20") (pinfunction "SYSCLK_B20") (pintype "passive"))
    )
    (net (code "200") (name "unconnected-(X1A-TC-PadB27)") (class "Default")
      (node (ref "X1") (pin "B27") (pinfunction "TC_B27") (pintype "passive"))
    )
    (net (code "201") (name "unconnected-(X1B-+5V-PadD16)") (class "Default")
      (node (ref "X1") (pin "D16") (pinfunction "+5V_D16") (pintype "passive"))
    )
    (net (code "202") (name "unconnected-(X1B-0V-PadC0)") (class "Default")
      (node (ref "X1") (pin "C0") (pinfunction "0V_C0") (pintype "passive"))
    )
    (net (code "203") (name "unconnected-(X1B-0V-PadD0)") (class "Default")
      (node (ref "X1") (pin "D0") (pinfunction "0V_D0") (pintype "passive"))
    )
    (net (code "204") (name "unconnected-(X1B-0V-PadD18)") (class "Default")
      (node (ref "X1") (pin "D18") (pinfunction "0V_D18") (pintype "passive"))
    )
    (net (code "205") (name "unconnected-(X1B-0V-PadD19)") (class "Default")
      (node (ref "X1") (pin "D19") (pinfunction "0V_D19") (pintype "passive"))
    )
    (net (code "206") (name "unconnected-(X1B-DACK0-PadD8)") (class "Default")
      (node (ref "X1") (pin "D8") (pinfunction "DACK0_D8") (pintype "passive"))
    )
    (net (code "207") (name "unconnected-(X1B-DACK5-PadD10)") (class "Default")
      (node (ref "X1") (pin "D10") (pinfunction "DACK5_D10") (pintype "passive"))
    )
    (net (code "208") (name "unconnected-(X1B-DACK6-PadD12)") (class "Default")
      (node (ref "X1") (pin "D12") (pinfunction "DACK6_D12") (pintype "passive"))
    )
    (net (code "209") (name "unconnected-(X1B-DACK7-PadD14)") (class "Default")
      (node (ref "X1") (pin "D14") (pinfunction "DACK7_D14") (pintype "passive"))
    )
    (net (code "210") (name "unconnected-(X1B-DRQ0-PadD9)") (class "Default")
      (node (ref "X1") (pin "D9") (pinfunction "DRQ0_D9") (pintype "passive"))
    )
    (net (code "211") (name "unconnected-(X1B-DRQ5-PadD11)") (class "Default")
      (node (ref "X1") (pin "D11") (pinfunction "DRQ5_D11") (pintype "passive"))
    )
    (net (code "212") (name "unconnected-(X1B-DRQ6-PadD13)") (class "Default")
      (node (ref "X1") (pin "D13") (pinfunction "DRQ6_D13") (pintype "passive"))
    )
    (net (code "213") (name "unconnected-(X1B-DRQ7-PadD15)") (class "Default")
      (node (ref "X1") (pin "D15") (pinfunction "DRQ7_D15") (pintype "passive"))
    )
    (net (code "214") (name "unconnected-(X1B-IOCS16-PadD2)") (class "Default")
      (node (ref "X1") (pin "D2") (pinfunction "IOCS16_D2") (pintype "passive"))
    )
    (net (code "215") (name "unconnected-(X1B-IRQ10-PadD3)") (class "Default")
      (node (ref "X1") (pin "D3") (pinfunction "IRQ10_D3") (pintype "passive"))
    )
    (net (code "216") (name "unconnected-(X1B-IRQ11-PadD4)") (class "Default")
      (node (ref "X1") (pin "D4") (pinfunction "IRQ11_D4") (pintype "passive"))
    )
    (net (code "217") (name "unconnected-(X1B-IRQ12-PadD5)") (class "Default")
      (node (ref "X1") (pin "D5") (pinfunction "IRQ12_D5") (pintype "passive"))
    )
    (net (code "218") (name "unconnected-(X1B-IRQ14-PadD7)") (class "Default")
      (node (ref "X1") (pin "D7") (pinfunction "IRQ14_D7") (pintype "passive"))
    )
    (net (code "219") (name "unconnected-(X1B-IRQ15-PadD6)") (class "Default")
      (node (ref "X1") (pin "D6") (pinfunction "IRQ15_D6") (pintype "passive"))
    )
    (net (code "220") (name "unconnected-(X1B-KEY-PadC19)") (class "Default")
      (node (ref "X1") (pin "C19") (pinfunction "KEY_C19") (pintype "passive"))
    )
    (net (code "221") (name "unconnected-(X1B-LA17-PadC8)") (class "Default")
      (node (ref "X1") (pin "C8") (pinfunction "LA17_C8") (pintype "passive"))
    )
    (net (code "222") (name "unconnected-(X1B-LA18-PadC7)") (class "Default")
      (node (ref "X1") (pin "C7") (pinfunction "LA18_C7") (pintype "passive"))
    )
    (net (code "223") (name "unconnected-(X1B-LA19-PadC6)") (class "Default")
      (node (ref "X1") (pin "C6") (pinfunction "LA19_C6") (pintype "passive"))
    )
    (net (code "224") (name "unconnected-(X1B-LA20-PadC5)") (class "Default")
      (node (ref "X1") (pin "C5") (pinfunction "LA20_C5") (pintype "passive"))
    )
    (net (code "225") (name "unconnected-(X1B-LA21-PadC4)") (class "Default")
      (node (ref "X1") (pin "C4") (pinfunction "LA21_C4") (pintype "passive"))
    )
    (net (code "226") (name "unconnected-(X1B-LA22-PadC3)") (class "Default")
      (node (ref "X1") (pin "C3") (pinfunction "LA22_C3") (pintype "passive"))
    )
    (net (code "227") (name "unconnected-(X1B-LA23-PadC2)") (class "Default")
      (node (ref "X1") (pin "C2") (pinfunction "LA23_C2") (pintype "passive"))
    )
    (net (code "228") (name "unconnected-(X1B-MASTER-PadD17)") (class "Default")
      (node (ref "X1") (pin "D17") (pinfunction "MASTER_D17") (pintype "passive"))
    )
    (net (code "229") (name "unconnected-(X1B-MEMCS16-PadD1)") (class "Default")
      (node (ref "X1") (pin "D1") (pinfunction "MEMCS16_D1") (pintype "passive"))
    )
    (net (code "230") (name "unconnected-(X1B-MEMR-PadC9)") (class "Default")
      (node (ref "X1") (pin "C9") (pinfunction "MEMR_C9") (pintype "passive"))
    )
    (net (code "231") (name "unconnected-(X1B-MEMW-PadC10)") (class "Default")
      (node (ref "X1") (pin "C10") (pinfunction "MEMW_C10") (pintype "passive"))
    )
    (net (code "232") (name "unconnected-(X1B-SBHE-PadC1)") (class "Default")
      (node (ref "X1") (pin "C1") (pinfunction "SBHE_C1") (pintype "passive"))
    )
    (net (code "233") (name "unconnected-(X1B-SD8-PadC11)") (class "Default")
      (node (ref "X1") (pin "C11") (pinfunction "SD8_C11") (pintype "passive"))
    )
    (net (code "234") (name "unconnected-(X1B-SD9-PadC12)") (class "Default")
      (node (ref "X1") (pin "C12") (pinfunction "SD9_C12") (pintype "passive"))
    )
    (net (code "235") (name "unconnected-(X1B-SD10-PadC13)") (class "Default")
      (node (ref "X1") (pin "C13") (pinfunction "SD10_C13") (pintype "passive"))
    )
    (net (code "236") (name "unconnected-(X1B-SD11-PadC14)") (class "Default")
      (node (ref "X1") (pin "C14") (pinfunction "SD11_C14") (pintype "passive"))
    )
    (net (code "237") (name "unconnected-(X1B-SD12-PadC15)") (class "Default")
      (node (ref "X1") (pin "C15") (pinfunction "SD12_C15") (pintype "passive"))
    )
    (net (code "238") (name "unconnected-(X1B-SD13-PadC16)") (class "Default")
      (node (ref "X1") (pin "C16") (pinfunction "SD13_C16") (pintype "passive"))
    )
    (net (code "239") (name "unconnected-(X1B-SD14-PadC17)") (class "Default")
      (node (ref "X1") (pin "C17") (pinfunction "SD14_C17") (pintype "passive"))
    )
    (net (code "240") (name "unconnected-(X1B-SD15-PadC18)") (class "Default")
      (node (ref "X1") (pin "C18") (pinfunction "SD15_C18") (pintype "passive"))
    )
  )
)
